# akabeacon_square_MDBT40.net
KiCad netlist of a schematic drawn in EAGLE
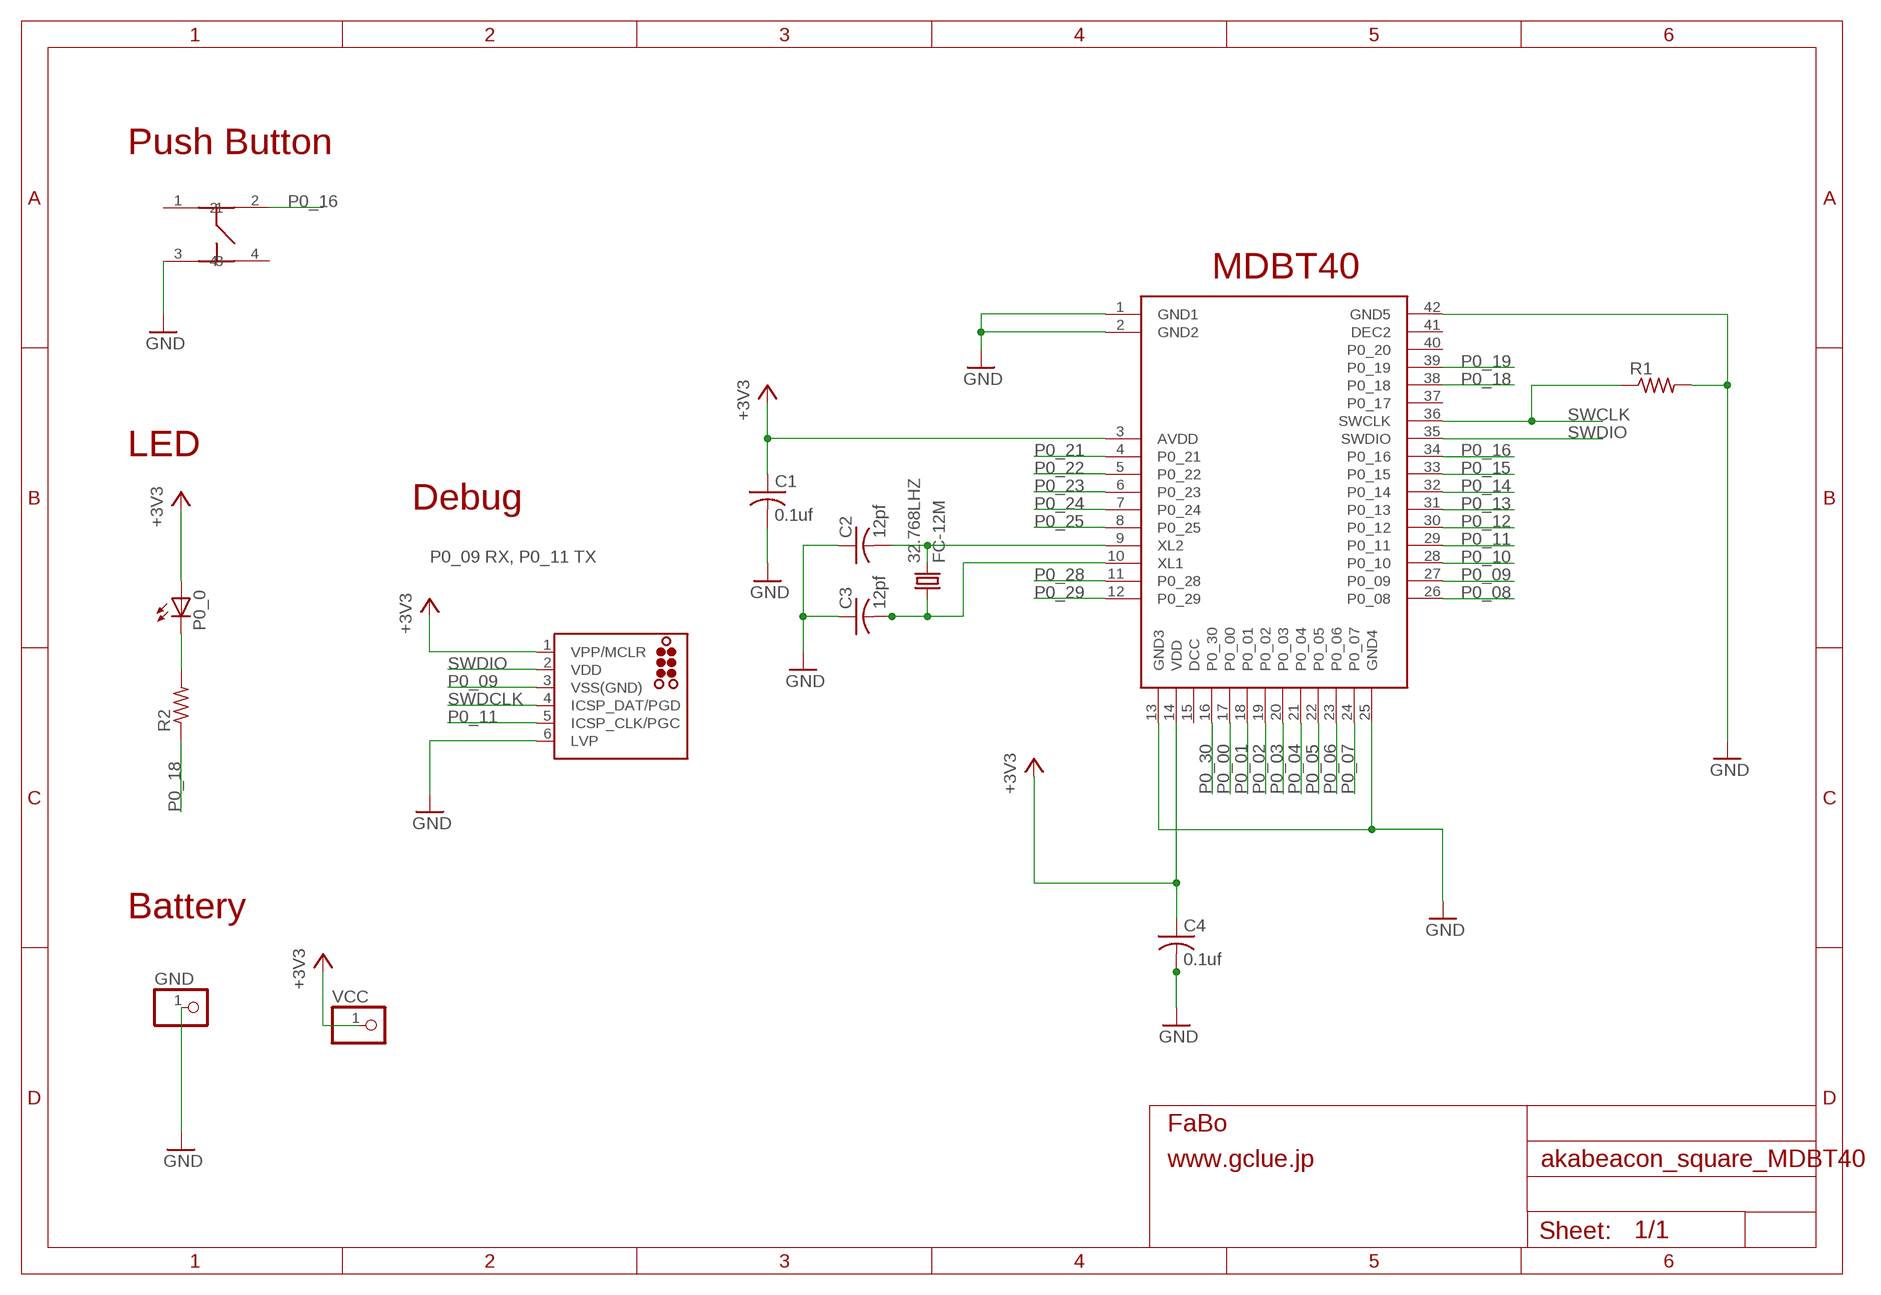
[diagram p0: schematic, sheet 1]

(export (version "E")
  (design (tool "Eeschema 10.0.6"))
  (components
    (comp (ref "32.768LHZ")
      (value "FC-12M")
      (footprint "eagle-import:FC-12M")
      (libsource (lib "eagle-import") (part "FC-12M"))
    )
    (comp (ref "C1")
      (value "0.1uf")
      (footprint "eagle-import:C0603")
      (libsource (lib "eagle-import") (part "C-USC0603"))
    )
    (comp (ref "C2")
      (value "12pf")
      (footprint "eagle-import:C0603")
      (libsource (lib "eagle-import") (part "C-USC0603"))
    )
    (comp (ref "C3")
      (value "12pf")
      (footprint "eagle-import:C0603")
      (libsource (lib "eagle-import") (part "C-USC0603"))
    )
    (comp (ref "C4")
      (value "0.1uf")
      (footprint "eagle-import:C0603")
      (libsource (lib "eagle-import") (part "C-USC0603"))
    )
    (comp (ref "GND")
      (value "PINHD-1X1CB")
      (footprint "eagle-import:1X01-CLEANBIG")
      (libsource (lib "eagle-import") (part "PINHD-1X1CB"))
    )
    (comp (ref "J2")
      (value "TC2030-MCP")
      (footprint "eagle-import:TC2030-MCP")
      (libsource (lib "eagle-import") (part "TC2030-MCP"))
    )
    (comp (ref "P0_0")
      (value "LEDCHIP-LED0603")
      (footprint "eagle-import:CHIP-LED0603")
      (libsource (lib "eagle-import") (part "LEDCHIP-LED0603"))
    )
    (comp (ref "R1")
      (value "R-US_R0603")
      (footprint "eagle-import:R0603")
      (libsource (lib "eagle-import") (part "R-US_R0603"))
    )
    (comp (ref "R2")
      (value "R-US_R0603")
      (footprint "eagle-import:R0603")
      (libsource (lib "eagle-import") (part "R-US_R0603"))
    )
    (comp (ref "U$3")
      (value "RAYTAC-MDBT40")
      (footprint "eagle-import:RAYTAC-MDBT40")
      (libsource (lib "eagle-import") (part "RAYTAC-MDBT40"))
    )
    (comp (ref "U$6")
      (value "SWICTH-4P(KMR2)")
      (footprint "eagle-import:SWITCH-4P(KMR2)")
      (libsource (lib "eagle-import") (part "SWICTH-4P(KMR2)"))
    )
    (comp (ref "VCC")
      (value "PINHD-1X1CB")
      (footprint "eagle-import:1X01-CLEANBIG")
      (libsource (lib "eagle-import") (part "PINHD-1X1CB"))
    )
  )
  (nets
    (net (code "1") (name "+3V3") (class "Default")
      (node (ref "C1") (pin "1") (pinfunction "1_1") (pintype "passive"))
      (node (ref "C4") (pin "1") (pinfunction "1_1") (pintype "passive"))
      (node (ref "J2") (pin "1") (pinfunction "VPP/MCLR_1") (pintype "passive"))
      (node (ref "P0_0") (pin "A") (pinfunction "A_A") (pintype "passive"))
      (node (ref "U$3") (pin "14") (pinfunction "VDD_14") (pintype "bidirectional"))
      (node (ref "U$3") (pin "3") (pinfunction "AVDD_3") (pintype "bidirectional"))
      (node (ref "VCC") (pin "1") (pinfunction "1_1") (pintype "passive"))
    )
    (net (code "2") (name "/P0_00") (class "Default")
      (node (ref "U$3") (pin "17") (pinfunction "P0_00_17") (pintype "bidirectional"))
    )
    (net (code "3") (name "/P0_01") (class "Default")
      (node (ref "U$3") (pin "18") (pinfunction "P0_01_18") (pintype "bidirectional"))
    )
    (net (code "4") (name "/P0_02") (class "Default")
      (node (ref "U$3") (pin "19") (pinfunction "P0_02_19") (pintype "bidirectional"))
    )
    (net (code "5") (name "/P0_03") (class "Default")
      (node (ref "U$3") (pin "20") (pinfunction "P0_03_20") (pintype "bidirectional"))
    )
    (net (code "6") (name "/P0_04") (class "Default")
      (node (ref "U$3") (pin "21") (pinfunction "P0_04_21") (pintype "bidirectional"))
    )
    (net (code "7") (name "/P0_05") (class "Default")
      (node (ref "U$3") (pin "22") (pinfunction "P0_05_22") (pintype "bidirectional"))
    )
    (net (code "8") (name "/P0_06") (class "Default")
      (node (ref "U$3") (pin "23") (pinfunction "P0_06_23") (pintype "bidirectional"))
    )
    (net (code "9") (name "/P0_07") (class "Default")
      (node (ref "U$3") (pin "24") (pinfunction "P0_07_24") (pintype "bidirectional"))
    )
    (net (code "10") (name "/P0_08") (class "Default")
      (node (ref "U$3") (pin "26") (pinfunction "P0_08_26") (pintype "bidirectional"))
    )
    (net (code "11") (name "/P0_09") (class "Default")
      (node (ref "J2") (pin "3") (pinfunction "VSS(GND)_3") (pintype "power_in"))
      (node (ref "U$3") (pin "27") (pinfunction "P0_09_27") (pintype "bidirectional"))
    )
    (net (code "12") (name "/P0_10") (class "Default")
      (node (ref "U$3") (pin "28") (pinfunction "P0_10_28") (pintype "bidirectional"))
    )
    (net (code "13") (name "/P0_11") (class "Default")
      (node (ref "J2") (pin "5") (pinfunction "ICSP_CLK/PGC_5") (pintype "output"))
      (node (ref "U$3") (pin "29") (pinfunction "P0_11_29") (pintype "bidirectional"))
    )
    (net (code "14") (name "/P0_12") (class "Default")
      (node (ref "U$3") (pin "30") (pinfunction "P0_12_30") (pintype "bidirectional"))
    )
    (net (code "15") (name "/P0_13") (class "Default")
      (node (ref "U$3") (pin "31") (pinfunction "P0_13_31") (pintype "bidirectional"))
    )
    (net (code "16") (name "/P0_14") (class "Default")
      (node (ref "U$3") (pin "32") (pinfunction "P0_14_32") (pintype "bidirectional"))
    )
    (net (code "17") (name "/P0_15") (class "Default")
      (node (ref "U$3") (pin "33") (pinfunction "P0_15_33") (pintype "bidirectional"))
    )
    (net (code "18") (name "/P0_16") (class "Default")
      (node (ref "U$3") (pin "34") (pinfunction "P0_16_34") (pintype "bidirectional"))
      (node (ref "U$6") (pin "2") (pinfunction "2_2") (pintype "bidirectional"))
    )
    (net (code "19") (name "/P0_18") (class "Default")
      (node (ref "R2") (pin "1") (pinfunction "1_1") (pintype "passive"))
      (node (ref "U$3") (pin "38") (pinfunction "P0_18_38") (pintype "bidirectional"))
    )
    (net (code "20") (name "/P0_19") (class "Default")
      (node (ref "U$3") (pin "39") (pinfunction "P0_19_39") (pintype "bidirectional"))
    )
    (net (code "21") (name "/P0_21") (class "Default")
      (node (ref "U$3") (pin "4") (pinfunction "P0_21_4") (pintype "bidirectional"))
    )
    (net (code "22") (name "/P0_22") (class "Default")
      (node (ref "U$3") (pin "5") (pinfunction "P0_22_5") (pintype "bidirectional"))
    )
    (net (code "23") (name "/P0_23") (class "Default")
      (node (ref "U$3") (pin "6") (pinfunction "P0_23_6") (pintype "bidirectional"))
    )
    (net (code "24") (name "/P0_24") (class "Default")
      (node (ref "U$3") (pin "7") (pinfunction "P0_24_7") (pintype "bidirectional"))
    )
    (net (code "25") (name "/P0_25") (class "Default")
      (node (ref "U$3") (pin "8") (pinfunction "P0_25_8") (pintype "bidirectional"))
    )
    (net (code "26") (name "/P0_28") (class "Default")
      (node (ref "U$3") (pin "11") (pinfunction "P0_28_11") (pintype "bidirectional"))
    )
    (net (code "27") (name "/P0_29") (class "Default")
      (node (ref "U$3") (pin "12") (pinfunction "P0_29_12") (pintype "bidirectional"))
    )
    (net (code "28") (name "/P0_30") (class "Default")
      (node (ref "U$3") (pin "16") (pinfunction "P0_30_16") (pintype "bidirectional"))
    )
    (net (code "29") (name "/SWCLK") (class "Default")
      (node (ref "R1") (pin "1") (pinfunction "1_1") (pintype "passive"))
      (node (ref "U$3") (pin "36") (pinfunction "SWCLK_36") (pintype "bidirectional"))
    )
    (net (code "30") (name "/SWDCLK") (class "Default")
      (node (ref "J2") (pin "4") (pinfunction "ICSP_DAT/PGD_4") (pintype "bidirectional"))
    )
    (net (code "31") (name "/SWDIO") (class "Default")
      (node (ref "J2") (pin "2") (pinfunction "VDD_2") (pintype "power_in"))
      (node (ref "U$3") (pin "35") (pinfunction "SWDIO_35") (pintype "bidirectional"))
    )
    (net (code "32") (name "GND") (class "Default")
      (node (ref "C1") (pin "2") (pinfunction "2_2") (pintype "passive"))
      (node (ref "C2") (pin "1") (pinfunction "1_1") (pintype "passive"))
      (node (ref "C3") (pin "1") (pinfunction "1_1") (pintype "passive"))
      (node (ref "C4") (pin "2") (pinfunction "2_2") (pintype "passive"))
      (node (ref "GND") (pin "1") (pinfunction "1_1") (pintype "passive"))
      (node (ref "J2") (pin "6") (pinfunction "LVP_6") (pintype "bidirectional"))
      (node (ref "R1") (pin "2") (pinfunction "2_2") (pintype "passive"))
      (node (ref "U$3") (pin "1") (pinfunction "GND1_1") (pintype "bidirectional"))
      (node (ref "U$3") (pin "13") (pinfunction "GND3_13") (pintype "bidirectional"))
      (node (ref "U$3") (pin "2") (pinfunction "GND2_2") (pintype "bidirectional"))
      (node (ref "U$3") (pin "25") (pinfunction "GND4_25") (pintype "bidirectional"))
      (node (ref "U$3") (pin "42") (pinfunction "GND5_42") (pintype "bidirectional"))
      (node (ref "U$6") (pin "3") (pinfunction "3_3") (pintype "bidirectional"))
    )
    (net (code "33") (name "Net-(P0_0-PadC)") (class "Default")
      (node (ref "P0_0") (pin "C") (pinfunction "C_C") (pintype "passive"))
      (node (ref "R2") (pin "2") (pinfunction "2_2") (pintype "passive"))
    )
    (net (code "34") (name "Net-(U$3-XL1)") (class "Default")
      (node (ref "32.768LHZ") (pin "1") (pinfunction "1_1") (pintype "passive"))
      (node (ref "C3") (pin "2") (pinfunction "2_2") (pintype "passive"))
      (node (ref "U$3") (pin "10") (pinfunction "XL1_10") (pintype "bidirectional"))
    )
    (net (code "35") (name "Net-(U$3-XL2)") (class "Default")
      (node (ref "32.768LHZ") (pin "2") (pinfunction "2_2") (pintype "passive"))
      (node (ref "C2") (pin "2") (pinfunction "2_2") (pintype "passive"))
      (node (ref "U$3") (pin "9") (pinfunction "XL2_9") (pintype "bidirectional"))
    )
    (net (code "36") (name "unconnected-(U$3-DCC-Pad15)") (class "Default")
      (node (ref "U$3") (pin "15") (pinfunction "DCC_15") (pintype "bidirectional"))
    )
    (net (code "37") (name "unconnected-(U$3-DEC2-Pad41)") (class "Default")
      (node (ref "U$3") (pin "41") (pinfunction "DEC2_41") (pintype "bidirectional"))
    )
    (net (code "38") (name "unconnected-(U$3-P0_17-Pad37)") (class "Default")
      (node (ref "U$3") (pin "37") (pinfunction "P0_17_37") (pintype "bidirectional"))
    )
    (net (code "39") (name "unconnected-(U$3-P0_20-Pad40)") (class "Default")
      (node (ref "U$3") (pin "40") (pinfunction "P0_20_40") (pintype "bidirectional"))
    )
    (net (code "40") (name "unconnected-(U$6-Pad1)") (class "Default")
      (node (ref "U$6") (pin "1") (pinfunction "1_1") (pintype "bidirectional"))
    )
    (net (code "41") (name "unconnected-(U$6-Pad4)") (class "Default")
      (node (ref "U$6") (pin "4") (pinfunction "4_4") (pintype "bidirectional"))
    )
  )
)
